# Fade.net
KiCad netlist of a schematic drawn in EAGLE
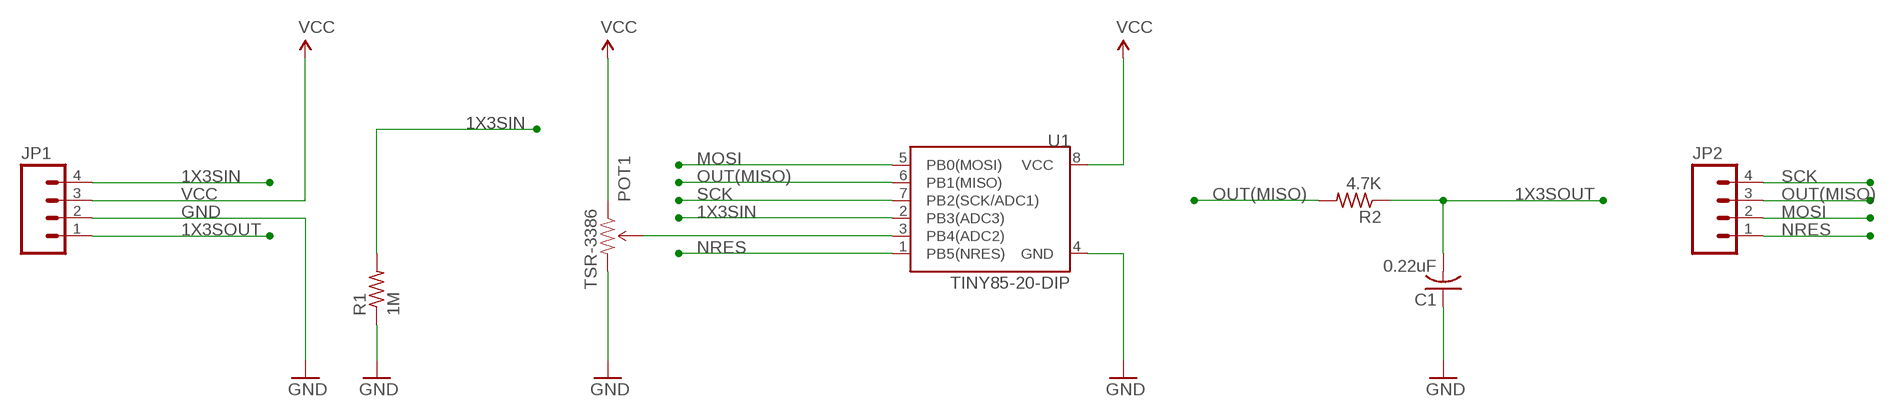
[diagram p0: schematic, sheet 1]

(export (version "E")
  (design (tool "Eeschema 10.0.6"))
  (components
    (comp (ref "C1")
      (value "0.22uF")
      (footprint "eagle-import:C0402")
      (libsource (lib "eagle-import") (part "C-USC0402"))
    )
    (comp (ref "JP1")
      (value "M04PTH")
      (footprint "eagle-import:1X04")
      (libsource (lib "eagle-import") (part "M04PTH"))
    )
    (comp (ref "JP2")
      (value "M04PTH")
      (footprint "eagle-import:1X04")
      (libsource (lib "eagle-import") (part "M04PTH"))
    )
    (comp (ref "POT1")
      (value "TSR-3386")
      (footprint "eagle-import:3386U")
      (libsource (lib "eagle-import") (part "TRIMPOT-PTH-KNOB"))
    )
    (comp (ref "R1")
      (value "1M")
      (footprint "eagle-import:R0603")
      (libsource (lib "eagle-import") (part "R-US_R0603"))
    )
    (comp (ref "R2")
      (value "4.7K")
      (footprint "eagle-import:R0603")
      (libsource (lib "eagle-import") (part "R-US_R0603"))
    )
    (comp (ref "U1")
      (value "TINY85-20-DIP")
      (footprint "eagle-import:DIP08")
      (libsource (lib "eagle-import") (part "ATTINY45TINY85-20-DIP"))
    )
  )
  (nets
    (net (code "1") (name "/1X3SIN") (class "Default")
      (node (ref "JP1") (pin "4") (pinfunction "4_4") (pintype "passive"))
      (node (ref "R1") (pin "2") (pinfunction "2_2") (pintype "passive"))
      (node (ref "U1") (pin "2") (pinfunction "PB3(ADC3)_2") (pintype "bidirectional"))
    )
    (net (code "2") (name "/1X3SOUT") (class "Default")
      (node (ref "C1") (pin "2") (pinfunction "2_2") (pintype "passive"))
      (node (ref "JP1") (pin "1") (pinfunction "1_1") (pintype "passive"))
      (node (ref "R2") (pin "1") (pinfunction "1_1") (pintype "passive"))
    )
    (net (code "3") (name "/MOSI") (class "Default")
      (node (ref "JP2") (pin "2") (pinfunction "2_2") (pintype "passive"))
      (node (ref "U1") (pin "5") (pinfunction "PB0(MOSI)_5") (pintype "bidirectional"))
    )
    (net (code "4") (name "/NRES") (class "Default")
      (node (ref "JP2") (pin "1") (pinfunction "1_1") (pintype "passive"))
      (node (ref "U1") (pin "1") (pinfunction "PB5(NRES)_1") (pintype "bidirectional"))
    )
    (net (code "5") (name "/OUT(MISO)") (class "Default")
      (node (ref "JP2") (pin "3") (pinfunction "3_3") (pintype "passive"))
      (node (ref "R2") (pin "2") (pinfunction "2_2") (pintype "passive"))
      (node (ref "U1") (pin "6") (pinfunction "PB1(MISO)_6") (pintype "bidirectional"))
    )
    (net (code "6") (name "/SCK") (class "Default")
      (node (ref "JP2") (pin "4") (pinfunction "4_4") (pintype "passive"))
      (node (ref "U1") (pin "7") (pinfunction "PB2(SCK/ADC1)_7") (pintype "bidirectional"))
    )
    (net (code "7") (name "GND") (class "Default")
      (node (ref "C1") (pin "1") (pinfunction "1_1") (pintype "passive"))
      (node (ref "JP1") (pin "2") (pinfunction "2_2") (pintype "passive"))
      (node (ref "POT1") (pin "3") (pinfunction "CW_3") (pintype "passive"))
      (node (ref "R1") (pin "1") (pinfunction "1_1") (pintype "passive"))
      (node (ref "U1") (pin "4") (pinfunction "GND_4") (pintype "bidirectional"))
    )
    (net (code "8") (name "Net-(POT1-WIPER)") (class "Default")
      (node (ref "POT1") (pin "2") (pinfunction "WIPER_2") (pintype "passive"))
      (node (ref "U1") (pin "3") (pinfunction "PB4(ADC2)_3") (pintype "bidirectional"))
    )
    (net (code "9") (name "VCC") (class "Default")
      (node (ref "JP1") (pin "3") (pinfunction "3_3") (pintype "passive"))
      (node (ref "POT1") (pin "1") (pinfunction "CCW_1") (pintype "passive"))
      (node (ref "U1") (pin "8") (pinfunction "VCC_8") (pintype "bidirectional"))
    )
  )
)
